# e0-dev-v006.net
KiCad netlist of a schematic drawn in EAGLE
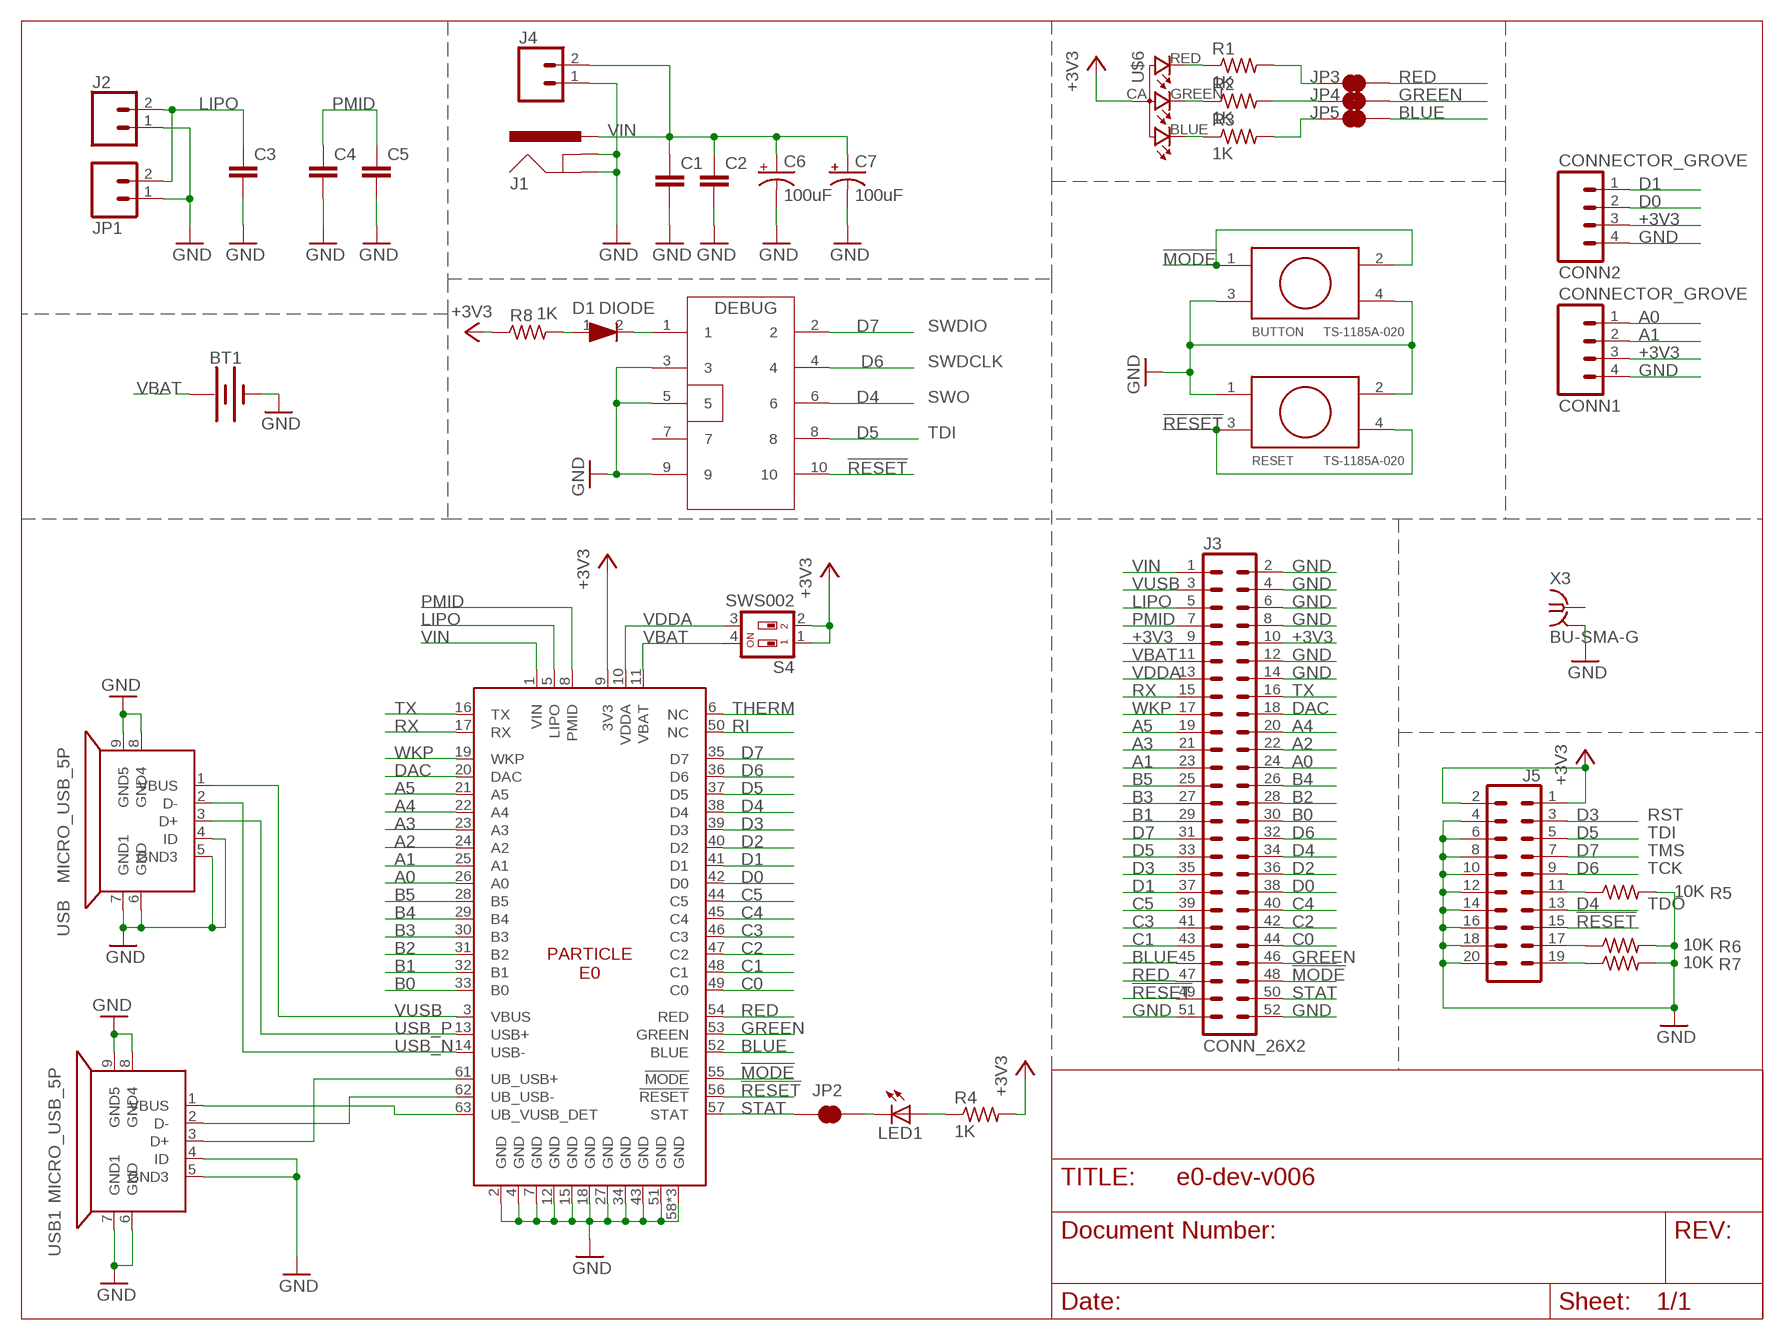
[diagram p0: schematic, sheet 1]

(export (version "E")
  (design (tool "Eeschema 10.0.6"))
  (components
    (comp (ref "BT1")
      (value "BATTERY-20MM_SMD")
      (footprint "eagle-import:BATTCON_20MM")
      (libsource (lib "eagle-import") (part "BATTERY-20MM_SMD"))
    )
    (comp (ref "BUTTON")
      (value "TS-1185A-020")
      (footprint "eagle-import:TS-1185A-020")
      (libsource (lib "eagle-import") (part "TS-1185A-020"))
    )
    (comp (ref "C1")
      (value "C-EUC0805")
      (footprint "eagle-import:C0805")
      (libsource (lib "eagle-import") (part "C-EUC0805"))
    )
    (comp (ref "C2")
      (value "C-EUC0805")
      (footprint "eagle-import:C0805")
      (libsource (lib "eagle-import") (part "C-EUC0805"))
    )
    (comp (ref "C3")
      (value "C-EUC0805")
      (footprint "eagle-import:C0805")
      (libsource (lib "eagle-import") (part "C-EUC0805"))
    )
    (comp (ref "C4")
      (value "C-EUC0805")
      (footprint "eagle-import:C0805")
      (libsource (lib "eagle-import") (part "C-EUC0805"))
    )
    (comp (ref "C5")
      (value "C-EUC0805")
      (footprint "eagle-import:C0805")
      (libsource (lib "eagle-import") (part "C-EUC0805"))
    )
    (comp (ref "C6")
      (value "100uF")
      (footprint "eagle-import:PANASONIC_D")
      (libsource (lib "eagle-import") (part "100UF-POLAR-25V-20%(ELEC)"))
    )
    (comp (ref "C7")
      (value "100uF")
      (footprint "eagle-import:PANASONIC_D")
      (libsource (lib "eagle-import") (part "100UF-POLAR-25V-20%(ELEC)"))
    )
    (comp (ref "CONN1")
      (value "CONNECTOR_GROVE")
      (footprint "eagle-import:CONNCTOR_GROVE")
      (libsource (lib "eagle-import") (part "CONNECTOR_GROVE"))
    )
    (comp (ref "CONN2")
      (value "CONNECTOR_GROVE")
      (footprint "eagle-import:CONNCTOR_GROVE")
      (libsource (lib "eagle-import") (part "CONNECTOR_GROVE"))
    )
    (comp (ref "D1")
      (value "DIODE")
      (footprint "eagle-import:SOD-323")
      (libsource (lib "eagle-import") (part "DIODESOD323"))
    )
    (comp (ref "DEBUG")
      (value "CON5X2")
      (footprint "eagle-import:CON5X2_1.27")
      (libsource (lib "eagle-import") (part "CON5X2"))
    )
    (comp (ref "J1")
      (value "POWER_JACKSLT")
      (footprint "eagle-import:POWER_JACK_SLOT")
      (libsource (lib "eagle-import") (part "POWER_JACKSLT"))
    )
    (comp (ref "J2")
      (value "CONN_021X02_NO_SILK")
      (footprint "eagle-import:1X02_NO_SILK")
      (libsource (lib "eagle-import") (part "CONN_021X02_NO_SILK"))
    )
    (comp (ref "J3")
      (value "CONN_26X2")
      (footprint "eagle-import:2X26")
      (libsource (lib "eagle-import") (part "CONN_26X2"))
    )
    (comp (ref "J4")
      (value "CONN_021X02_NO_SILK")
      (footprint "eagle-import:1X02_NO_SILK")
      (libsource (lib "eagle-import") (part "CONN_021X02_NO_SILK"))
    )
    (comp (ref "J5")
      (value "CONN_10X2NOSILK")
      (footprint "eagle-import:2X10_NOSILK")
      (libsource (lib "eagle-import") (part "CONN_10X2NOSILK"))
    )
    (comp (ref "JP1")
      (value "M02-JST-2MM-SMT")
      (footprint "eagle-import:JST-2-SMD@1")
      (libsource (lib "eagle-import") (part "M02-JST-2MM-SMT"))
    )
    (comp (ref "JP2")
      (value "JUMPER-SMT_2_NC_TRACE_NO-SILK")
      (footprint "eagle-import:SMT-JUMPER_2_NC_TRACE_NO-SILK")
      (libsource (lib "eagle-import") (part "JUMPER-SMT_2_NC_TRACE_NO-SILK"))
    )
    (comp (ref "JP3")
      (value "JUMPER-SMT_2_NC_TRACE_NO-SILK")
      (footprint "eagle-import:SMT-JUMPER_2_NC_TRACE_NO-SILK")
      (libsource (lib "eagle-import") (part "JUMPER-SMT_2_NC_TRACE_NO-SILK"))
    )
    (comp (ref "JP4")
      (value "JUMPER-SMT_2_NC_TRACE_NO-SILK")
      (footprint "eagle-import:SMT-JUMPER_2_NC_TRACE_NO-SILK")
      (libsource (lib "eagle-import") (part "JUMPER-SMT_2_NC_TRACE_NO-SILK"))
    )
    (comp (ref "JP5")
      (value "JUMPER-SMT_2_NC_TRACE_NO-SILK")
      (footprint "eagle-import:SMT-JUMPER_2_NC_TRACE_NO-SILK")
      (libsource (lib "eagle-import") (part "JUMPER-SMT_2_NC_TRACE_NO-SILK"))
    )
    (comp (ref "LED1")
      (value "LED0603")
      (footprint "eagle-import:LED-0603")
      (libsource (lib "eagle-import") (part "LED0603"))
    )
    (comp (ref "R1")
      (value "1K")
      (footprint "eagle-import:R0603")
      (libsource (lib "eagle-import") (part "R-US_R0603"))
    )
    (comp (ref "R2")
      (value "1K")
      (footprint "eagle-import:R0603")
      (libsource (lib "eagle-import") (part "R-US_R0603"))
    )
    (comp (ref "R3")
      (value "1K")
      (footprint "eagle-import:R0603")
      (libsource (lib "eagle-import") (part "R-US_R0603"))
    )
    (comp (ref "R4")
      (value "1K")
      (footprint "eagle-import:R0603")
      (libsource (lib "eagle-import") (part "R-US_R0603"))
    )
    (comp (ref "R5")
      (value "10K")
      (footprint "eagle-import:R0603")
      (libsource (lib "eagle-import") (part "R-US_R0603"))
    )
    (comp (ref "R6")
      (value "10K")
      (footprint "eagle-import:R0603")
      (libsource (lib "eagle-import") (part "R-US_R0603"))
    )
    (comp (ref "R7")
      (value "10K")
      (footprint "eagle-import:R0603")
      (libsource (lib "eagle-import") (part "R-US_R0603"))
    )
    (comp (ref "R8")
      (value "1K")
      (footprint "eagle-import:R0603")
      (libsource (lib "eagle-import") (part "R-US_R0603"))
    )
    (comp (ref "RESET")
      (value "TS-1185A-020")
      (footprint "eagle-import:TS-1185A-020")
      (libsource (lib "eagle-import") (part "TS-1185A-020"))
    )
    (comp (ref "S4")
      (value "SWS002")
      (footprint "eagle-import:SMS-002")
      (libsource (lib "eagle-import") (part "SWS002"))
    )
    (comp (ref "U$6")
      (value "RGB-LED-CLMVB-FKARGB")
      (footprint "eagle-import:PLCC4-2MM-RGB")
      (libsource (lib "eagle-import") (part "RGB-LED-CLMVB-FKARGB"))
    )
    (comp (ref "U1")
      (value "E0_V005")
      (footprint "eagle-import:E0")
      (libsource (lib "eagle-import") (part "E0_V005"))
    )
    (comp (ref "USB")
      (value "MICRO_USB_5P")
      (footprint "eagle-import:MICRO_USB")
      (libsource (lib "eagle-import") (part "MICRO_USBMICRO_USB"))
    )
    (comp (ref "USB1")
      (value "MICRO_USB_5P")
      (footprint "eagle-import:MICRO_USB")
      (libsource (lib "eagle-import") (part "MICRO_USBMICRO_USB"))
    )
    (comp (ref "X3")
      (value "BU-SMA-G")
      (footprint "eagle-import:BU-SMA-G")
      (libsource (lib "eagle-import") (part "BU-SMA-G"))
    )
  )
  (nets
    (net (code "1") (name "+3V3") (class "Default")
      (node (ref "CONN1") (pin "3") (pinfunction "3_3") (pintype "passive"))
      (node (ref "CONN2") (pin "3") (pinfunction "3_3") (pintype "passive"))
      (node (ref "J3") (pin "10") (pinfunction "10_10") (pintype "passive"))
      (node (ref "J3") (pin "9") (pinfunction "9_9") (pintype "passive"))
      (node (ref "J5") (pin "1") (pinfunction "1_1") (pintype "passive"))
      (node (ref "J5") (pin "2") (pinfunction "2_2") (pintype "passive"))
      (node (ref "R4") (pin "2") (pinfunction "2_2") (pintype "passive"))
      (node (ref "R8") (pin "1") (pinfunction "1_1") (pintype "passive"))
      (node (ref "S4") (pin "1") (pinfunction "1_1") (pintype "passive"))
      (node (ref "S4") (pin "2") (pinfunction "2_2") (pintype "passive"))
      (node (ref "U$6") (pin "CA") (pinfunction "1_CA") (pintype "passive"))
      (node (ref "U1") (pin "9") (pinfunction "3V3_9") (pintype "bidirectional"))
    )
    (net (code "2") (name "/A0") (class "Default")
      (node (ref "CONN1") (pin "1") (pinfunction "1_1") (pintype "passive"))
      (node (ref "J3") (pin "24") (pinfunction "24_24") (pintype "passive"))
      (node (ref "U1") (pin "26") (pinfunction "A0_26") (pintype "bidirectional"))
    )
    (net (code "3") (name "/A1") (class "Default")
      (node (ref "CONN1") (pin "2") (pinfunction "2_2") (pintype "passive"))
      (node (ref "J3") (pin "23") (pinfunction "23_23") (pintype "passive"))
      (node (ref "U1") (pin "25") (pinfunction "A1_25") (pintype "bidirectional"))
    )
    (net (code "4") (name "/A2") (class "Default")
      (node (ref "J3") (pin "22") (pinfunction "22_22") (pintype "passive"))
      (node (ref "U1") (pin "24") (pinfunction "A2_24") (pintype "bidirectional"))
    )
    (net (code "5") (name "/A3") (class "Default")
      (node (ref "J3") (pin "21") (pinfunction "21_21") (pintype "passive"))
      (node (ref "U1") (pin "23") (pinfunction "A3_23") (pintype "bidirectional"))
    )
    (net (code "6") (name "/A4") (class "Default")
      (node (ref "J3") (pin "20") (pinfunction "20_20") (pintype "passive"))
      (node (ref "U1") (pin "22") (pinfunction "A4_22") (pintype "bidirectional"))
    )
    (net (code "7") (name "/A5") (class "Default")
      (node (ref "J3") (pin "19") (pinfunction "19_19") (pintype "passive"))
      (node (ref "U1") (pin "21") (pinfunction "A5_21") (pintype "bidirectional"))
    )
    (net (code "8") (name "/B0") (class "Default")
      (node (ref "J3") (pin "30") (pinfunction "30_30") (pintype "passive"))
      (node (ref "U1") (pin "33") (pinfunction "B0_33") (pintype "bidirectional"))
    )
    (net (code "9") (name "/B1") (class "Default")
      (node (ref "J3") (pin "29") (pinfunction "29_29") (pintype "passive"))
      (node (ref "U1") (pin "32") (pinfunction "B1_32") (pintype "bidirectional"))
    )
    (net (code "10") (name "/B2") (class "Default")
      (node (ref "J3") (pin "28") (pinfunction "28_28") (pintype "passive"))
      (node (ref "U1") (pin "31") (pinfunction "B2_31") (pintype "bidirectional"))
    )
    (net (code "11") (name "/B3") (class "Default")
      (node (ref "J3") (pin "27") (pinfunction "27_27") (pintype "passive"))
      (node (ref "U1") (pin "30") (pinfunction "B3_30") (pintype "bidirectional"))
    )
    (net (code "12") (name "/B4") (class "Default")
      (node (ref "J3") (pin "26") (pinfunction "26_26") (pintype "passive"))
      (node (ref "U1") (pin "29") (pinfunction "B4_29") (pintype "bidirectional"))
    )
    (net (code "13") (name "/B5") (class "Default")
      (node (ref "J3") (pin "25") (pinfunction "25_25") (pintype "passive"))
      (node (ref "U1") (pin "28") (pinfunction "B5_28") (pintype "bidirectional"))
    )
    (net (code "14") (name "/BLUE") (class "Default")
      (node (ref "J3") (pin "45") (pinfunction "45_45") (pintype "passive"))
      (node (ref "JP5") (pin "2") (pinfunction "2_2") (pintype "passive"))
      (node (ref "U1") (pin "52") (pinfunction "BLUE_52") (pintype "bidirectional"))
    )
    (net (code "15") (name "/C0") (class "Default")
      (node (ref "J3") (pin "44") (pinfunction "44_44") (pintype "passive"))
      (node (ref "U1") (pin "49") (pinfunction "C0_49") (pintype "bidirectional"))
    )
    (net (code "16") (name "/C1") (class "Default")
      (node (ref "J3") (pin "43") (pinfunction "43_43") (pintype "passive"))
      (node (ref "U1") (pin "48") (pinfunction "C1_48") (pintype "bidirectional"))
    )
    (net (code "17") (name "/C2") (class "Default")
      (node (ref "J3") (pin "42") (pinfunction "42_42") (pintype "passive"))
      (node (ref "U1") (pin "47") (pinfunction "C2_47") (pintype "bidirectional"))
    )
    (net (code "18") (name "/C3") (class "Default")
      (node (ref "J3") (pin "41") (pinfunction "41_41") (pintype "passive"))
      (node (ref "U1") (pin "46") (pinfunction "C3_46") (pintype "bidirectional"))
    )
    (net (code "19") (name "/C4") (class "Default")
      (node (ref "J3") (pin "40") (pinfunction "40_40") (pintype "passive"))
      (node (ref "U1") (pin "45") (pinfunction "C4_45") (pintype "bidirectional"))
    )
    (net (code "20") (name "/C5") (class "Default")
      (node (ref "J3") (pin "39") (pinfunction "39_39") (pintype "passive"))
      (node (ref "U1") (pin "44") (pinfunction "C5_44") (pintype "bidirectional"))
    )
    (net (code "21") (name "/D0") (class "Default")
      (node (ref "CONN2") (pin "2") (pinfunction "2_2") (pintype "passive"))
      (node (ref "J3") (pin "38") (pinfunction "38_38") (pintype "passive"))
      (node (ref "U1") (pin "42") (pinfunction "D0_42") (pintype "bidirectional"))
    )
    (net (code "22") (name "/D1") (class "Default")
      (node (ref "CONN2") (pin "1") (pinfunction "1_1") (pintype "passive"))
      (node (ref "J3") (pin "37") (pinfunction "37_37") (pintype "passive"))
      (node (ref "U1") (pin "41") (pinfunction "D1_41") (pintype "bidirectional"))
    )
    (net (code "23") (name "/D2") (class "Default")
      (node (ref "J3") (pin "36") (pinfunction "36_36") (pintype "passive"))
      (node (ref "U1") (pin "40") (pinfunction "D2_40") (pintype "bidirectional"))
    )
    (net (code "24") (name "/D3") (class "Default")
      (node (ref "J3") (pin "35") (pinfunction "35_35") (pintype "passive"))
      (node (ref "J5") (pin "3") (pinfunction "3_3") (pintype "passive"))
      (node (ref "U1") (pin "39") (pinfunction "D3_39") (pintype "bidirectional"))
    )
    (net (code "25") (name "/D4") (class "Default")
      (node (ref "DEBUG") (pin "6") (pinfunction "6_6") (pintype "bidirectional"))
      (node (ref "J3") (pin "34") (pinfunction "34_34") (pintype "passive"))
      (node (ref "J5") (pin "13") (pinfunction "13_13") (pintype "passive"))
      (node (ref "U1") (pin "38") (pinfunction "D4_38") (pintype "bidirectional"))
    )
    (net (code "26") (name "/D5") (class "Default")
      (node (ref "DEBUG") (pin "8") (pinfunction "8_8") (pintype "bidirectional"))
      (node (ref "J3") (pin "33") (pinfunction "33_33") (pintype "passive"))
      (node (ref "J5") (pin "5") (pinfunction "5_5") (pintype "passive"))
      (node (ref "U1") (pin "37") (pinfunction "D5_37") (pintype "bidirectional"))
    )
    (net (code "27") (name "/D6") (class "Default")
      (node (ref "DEBUG") (pin "4") (pinfunction "4_4") (pintype "bidirectional"))
      (node (ref "J3") (pin "32") (pinfunction "32_32") (pintype "passive"))
      (node (ref "J5") (pin "9") (pinfunction "9_9") (pintype "passive"))
      (node (ref "U1") (pin "36") (pinfunction "D6_36") (pintype "bidirectional"))
    )
    (net (code "28") (name "/D7") (class "Default")
      (node (ref "DEBUG") (pin "2") (pinfunction "2_2") (pintype "bidirectional"))
      (node (ref "J3") (pin "31") (pinfunction "31_31") (pintype "passive"))
      (node (ref "J5") (pin "7") (pinfunction "7_7") (pintype "passive"))
      (node (ref "U1") (pin "35") (pinfunction "D7_35") (pintype "bidirectional"))
    )
    (net (code "29") (name "/DAC") (class "Default")
      (node (ref "J3") (pin "18") (pinfunction "18_18") (pintype "passive"))
      (node (ref "U1") (pin "20") (pinfunction "DAC_20") (pintype "bidirectional"))
    )
    (net (code "30") (name "/GREEN") (class "Default")
      (node (ref "J3") (pin "46") (pinfunction "46_46") (pintype "passive"))
      (node (ref "JP4") (pin "2") (pinfunction "2_2") (pintype "passive"))
      (node (ref "U1") (pin "53") (pinfunction "GREEN_53") (pintype "bidirectional"))
    )
    (net (code "31") (name "/LIPO") (class "Default")
      (node (ref "C3") (pin "1") (pinfunction "1_1") (pintype "passive"))
      (node (ref "J2") (pin "2") (pinfunction "2_2") (pintype "passive"))
      (node (ref "J3") (pin "5") (pinfunction "5_5") (pintype "passive"))
      (node (ref "JP1") (pin "2") (pinfunction "1_2") (pintype "passive"))
      (node (ref "U1") (pin "5") (pinfunction "LIPO_5") (pintype "bidirectional"))
    )
    (net (code "32") (name "/PMID") (class "Default")
      (node (ref "C4") (pin "1") (pinfunction "1_1") (pintype "passive"))
      (node (ref "C5") (pin "1") (pinfunction "1_1") (pintype "passive"))
      (node (ref "J3") (pin "7") (pinfunction "7_7") (pintype "passive"))
      (node (ref "U1") (pin "8") (pinfunction "PMID_8") (pintype "bidirectional"))
    )
    (net (code "33") (name "/RED") (class "Default")
      (node (ref "J3") (pin "47") (pinfunction "47_47") (pintype "passive"))
      (node (ref "JP3") (pin "2") (pinfunction "2_2") (pintype "passive"))
      (node (ref "U1") (pin "54") (pinfunction "RED_54") (pintype "bidirectional"))
    )
    (net (code "34") (name "/RI") (class "Default")
      (node (ref "U1") (pin "50") (pinfunction "NC_50") (pintype "bidirectional"))
    )
    (net (code "35") (name "/RX") (class "Default")
      (node (ref "J3") (pin "15") (pinfunction "15_15") (pintype "passive"))
      (node (ref "U1") (pin "17") (pinfunction "RX_17") (pintype "bidirectional"))
    )
    (net (code "36") (name "/STAT") (class "Default")
      (node (ref "J3") (pin "50") (pinfunction "50_50") (pintype "passive"))
      (node (ref "JP2") (pin "1") (pinfunction "1_1") (pintype "passive"))
      (node (ref "U1") (pin "57") (pinfunction "STAT_57") (pintype "bidirectional"))
    )
    (net (code "37") (name "/THERM") (class "Default")
      (node (ref "U1") (pin "6") (pinfunction "NC_6") (pintype "bidirectional"))
    )
    (net (code "38") (name "/TX") (class "Default")
      (node (ref "J3") (pin "16") (pinfunction "16_16") (pintype "passive"))
      (node (ref "U1") (pin "16") (pinfunction "TX_16") (pintype "bidirectional"))
    )
    (net (code "39") (name "/USB_N") (class "Default")
      (node (ref "U1") (pin "14") (pinfunction "USB-_14") (pintype "bidirectional"))
      (node (ref "USB") (pin "2") (pinfunction "D-_2") (pintype "bidirectional"))
    )
    (net (code "40") (name "/USB_P") (class "Default")
      (node (ref "U1") (pin "13") (pinfunction "USB+_13") (pintype "bidirectional"))
      (node (ref "USB") (pin "3") (pinfunction "D+_3") (pintype "bidirectional"))
    )
    (net (code "41") (name "/VBAT") (class "Default")
      (node (ref "BT1") (pin "1") (pinfunction "+_1") (pintype "power_in"))
      (node (ref "J3") (pin "11") (pinfunction "11_11") (pintype "passive"))
      (node (ref "S4") (pin "4") (pinfunction "4_4") (pintype "passive"))
      (node (ref "U1") (pin "11") (pinfunction "VBAT_11") (pintype "bidirectional"))
    )
    (net (code "42") (name "/VDDA") (class "Default")
      (node (ref "J3") (pin "13") (pinfunction "13_13") (pintype "passive"))
      (node (ref "S4") (pin "3") (pinfunction "3_3") (pintype "passive"))
      (node (ref "U1") (pin "10") (pinfunction "VDDA_10") (pintype "bidirectional"))
    )
    (net (code "43") (name "/VIN") (class "Default")
      (node (ref "C1") (pin "1") (pinfunction "1_1") (pintype "passive"))
      (node (ref "C2") (pin "1") (pinfunction "1_1") (pintype "passive"))
      (node (ref "C6") (pin "+") (pinfunction "+_+") (pintype "passive"))
      (node (ref "C7") (pin "+") (pinfunction "+_+") (pintype "passive"))
      (node (ref "J1") (pin "PWR") (pinfunction "PWR_PWR") (pintype "bidirectional"))
      (node (ref "J3") (pin "1") (pinfunction "1_1") (pintype "passive"))
      (node (ref "J4") (pin "2") (pinfunction "2_2") (pintype "passive"))
      (node (ref "U1") (pin "1") (pinfunction "VIN_1") (pintype "bidirectional"))
    )
    (net (code "44") (name "/VUSB") (class "Default")
      (node (ref "J3") (pin "3") (pinfunction "3_3") (pintype "passive"))
      (node (ref "U1") (pin "3") (pinfunction "VBUS_3") (pintype "bidirectional"))
      (node (ref "USB") (pin "1") (pinfunction "VBUS_1") (pintype "bidirectional"))
    )
    (net (code "45") (name "/WKP") (class "Default")
      (node (ref "J3") (pin "17") (pinfunction "17_17") (pintype "passive"))
      (node (ref "U1") (pin "19") (pinfunction "WKP_19") (pintype "bidirectional"))
    )
    (net (code "46") (name "/~{MODE}") (class "Default")
      (node (ref "BUTTON") (pin "1") (pinfunction "P$1_1") (pintype "bidirectional"))
      (node (ref "BUTTON") (pin "2") (pinfunction "P$2_2") (pintype "bidirectional"))
      (node (ref "J3") (pin "48") (pinfunction "48_48") (pintype "passive"))
      (node (ref "U1") (pin "55") (pinfunction "~{MODE}_55") (pintype "bidirectional"))
    )
    (net (code "47") (name "/~{RESET}") (class "Default")
      (node (ref "DEBUG") (pin "10") (pinfunction "10_10") (pintype "bidirectional"))
      (node (ref "J3") (pin "49") (pinfunction "49_49") (pintype "passive"))
      (node (ref "J5") (pin "15") (pinfunction "15_15") (pintype "passive"))
      (node (ref "RESET") (pin "3") (pinfunction "P$3_3") (pintype "bidirectional"))
      (node (ref "RESET") (pin "4") (pinfunction "P$4_4") (pintype "bidirectional"))
      (node (ref "U1") (pin "56") (pinfunction "~{RESET}_56") (pintype "bidirectional"))
    )
    (net (code "48") (name "GND") (class "Default")
      (node (ref "BT1") (pin "2") (pinfunction "-_2") (pintype "power_in"))
      (node (ref "BUTTON") (pin "3") (pinfunction "P$3_3") (pintype "bidirectional"))
      (node (ref "BUTTON") (pin "4") (pinfunction "P$4_4") (pintype "bidirectional"))
      (node (ref "C1") (pin "2") (pinfunction "2_2") (pintype "passive"))
      (node (ref "C2") (pin "2") (pinfunction "2_2") (pintype "passive"))
      (node (ref "C3") (pin "2") (pinfunction "2_2") (pintype "passive"))
      (node (ref "C4") (pin "2") (pinfunction "2_2") (pintype "passive"))
      (node (ref "C5") (pin "2") (pinfunction "2_2") (pintype "passive"))
      (node (ref "C6") (pin "-") (pinfunction "-_-") (pintype "passive"))
      (node (ref "C7") (pin "-") (pinfunction "-_-") (pintype "passive"))
      (node (ref "CONN1") (pin "4") (pinfunction "4_4") (pintype "passive"))
      (node (ref "CONN2") (pin "4") (pinfunction "4_4") (pintype "passive"))
      (node (ref "DEBUG") (pin "3") (pinfunction "3_3") (pintype "bidirectional"))
      (node (ref "DEBUG") (pin "5") (pinfunction "5_5") (pintype "bidirectional"))
      (node (ref "DEBUG") (pin "9") (pinfunction "9_9") (pintype "bidirectional"))
      (node (ref "J1") (pin "GND@1") (pinfunction "GNDBREAK_GND@1") (pintype "bidirectional"))
      (node (ref "J1") (pin "GND@2") (pinfunction "GND_GND@2") (pintype "bidirectional"))
      (node (ref "J2") (pin "1") (pinfunction "1_1") (pintype "passive"))
      (node (ref "J3") (pin "12") (pinfunction "12_12") (pintype "passive"))
      (node (ref "J3") (pin "14") (pinfunction "14_14") (pintype "passive"))
      (node (ref "J3") (pin "2") (pinfunction "2_2") (pintype "passive"))
      (node (ref "J3") (pin "4") (pinfunction "4_4") (pintype "passive"))
      (node (ref "J3") (pin "51") (pinfunction "51_51") (pintype "passive"))
      (node (ref "J3") (pin "52") (pinfunction "52_52") (pintype "passive"))
      (node (ref "J3") (pin "6") (pinfunction "6_6") (pintype "passive"))
      (node (ref "J3") (pin "8") (pinfunction "8_8") (pintype "passive"))
      (node (ref "J4") (pin "1") (pinfunction "1_1") (pintype "passive"))
      (node (ref "J5") (pin "10") (pinfunction "10_10") (pintype "passive"))
      (node (ref "J5") (pin "12") (pinfunction "12_12") (pintype "passive"))
      (node (ref "J5") (pin "14") (pinfunction "14_14") (pintype "passive"))
      (node (ref "J5") (pin "16") (pinfunction "16_16") (pintype "passive"))
      (node (ref "J5") (pin "18") (pinfunction "18_18") (pintype "passive"))
      (node (ref "J5") (pin "20") (pinfunction "20_20") (pintype "passive"))
      (node (ref "J5") (pin "4") (pinfunction "4_4") (pintype "passive"))
      (node (ref "J5") (pin "6") (pinfunction "6_6") (pintype "passive"))
      (node (ref "J5") (pin "8") (pinfunction "8_8") (pintype "passive"))
      (node (ref "JP1") (pin "1") (pinfunction "2_1") (pintype "passive"))
      (node (ref "R5") (pin "2") (pinfunction "2_2") (pintype "passive"))
      (node (ref "R6") (pin "2") (pinfunction "2_2") (pintype "passive"))
      (node (ref "R7") (pin "2") (pinfunction "2_2") (pintype "passive"))
      (node (ref "RESET") (pin "1") (pinfunction "P$1_1") (pintype "bidirectional"))
      (node (ref "RESET") (pin "2") (pinfunction "P$2_2") (pintype "bidirectional"))
      (node (ref "U1") (pin "12") (pinfunction "GND_12") (pintype "bidirectional"))
      (node (ref "U1") (pin "15") (pinfunction "GND_15") (pintype "bidirectional"))
      (node (ref "U1") (pin "18") (pinfunction "GND_18") (pintype "bidirectional"))
      (node (ref "U1") (pin "2") (pinfunction "GND_2") (pintype "bidirectional"))
      (node (ref "U1") (pin "27") (pinfunction "GND_27") (pintype "bidirectional"))
      (node (ref "U1") (pin "34") (pinfunction "GND_34") (pintype "bidirectional"))
      (node (ref "U1") (pin "4") (pinfunction "GND_4") (pintype "bidirectional"))
      (node (ref "U1") (pin "43") (pinfunction "GND_43") (pintype "bidirectional"))
      (node (ref "U1") (pin "51") (pinfunction "GND_51") (pintype "bidirectional"))
      (node (ref "U1") (pin "58") (pinfunction "GND_58") (pintype "bidirectional"))
      (node (ref "U1") (pin "59") (pinfunction "GND_59") (pintype "bidirectional"))
      (node (ref "U1") (pin "60") (pinfunction "GND_60") (pintype "bidirectional"))
      (node (ref "U1") (pin "7") (pinfunction "GND_7") (pintype "bidirectional"))
      (node (ref "USB") (pin "4") (pinfunction "ID_4") (pintype "bidirectional"))
      (node (ref "USB") (pin "5") (pinfunction "GND3_5") (pintype "bidirectional"))
      (node (ref "USB") (pin "6") (pinfunction "GND_6") (pintype "bidirectional"))
      (node (ref "USB") (pin "7") (pinfunction "GND1_7") (pintype "bidirectional"))
      (node (ref "USB") (pin "8") (pinfunction "GND4_8") (pintype "bidirectional"))
      (node (ref "USB") (pin "9") (pinfunction "GND5_9") (pintype "bidirectional"))
      (node (ref "USB1") (pin "4") (pinfunction "ID_4") (pintype "bidirectional"))
      (node (ref "USB1") (pin "5") (pinfunction "GND3_5") (pintype "bidirectional"))
      (node (ref "USB1") (pin "6") (pinfunction "GND_6") (pintype "bidirectional"))
      (node (ref "USB1") (pin "7") (pinfunction "GND1_7") (pintype "bidirectional"))
      (node (ref "USB1") (pin "8") (pinfunction "GND4_8") (pintype "bidirectional"))
      (node (ref "USB1") (pin "9") (pinfunction "GND5_9") (pintype "bidirectional"))
      (node (ref "X3") (pin "2") (pinfunction "2_2") (pintype "passive"))
      (node (ref "X3") (pin "3") (pinfunction "2_3") (pintype "passive"))
      (node (ref "X3") (pin "4") (pinfunction "2_4") (pintype "passive"))
      (node (ref "X3") (pin "5") (pinfunction "2_5") (pintype "passive"))
    )
    (net (code "49") (name "Net-(D1-P$1)") (class "Default")
      (node (ref "D1") (pin "1") (pinfunction "P$1_1") (pintype "bidirectional"))
      (node (ref "R8") (pin "2") (pinfunction "2_2") (pintype "passive"))
    )
    (net (code "50") (name "Net-(D1-P$2)") (class "Default")
      (node (ref "D1") (pin "2") (pinfunction "P$2_2") (pintype "bidirectional"))
      (node (ref "DEBUG") (pin "1") (pinfunction "1_1") (pintype "bidirectional"))
    )
    (net (code "51") (name "Net-(J5-Pad11)") (class "Default")
      (node (ref "J5") (pin "11") (pinfunction "11_11") (pintype "passive"))
      (node (ref "R5") (pin "1") (pinfunction "1_1") (pintype "passive"))
    )
    (net (code "52") (name "Net-(J5-Pad17)") (class "Default")
      (node (ref "J5") (pin "17") (pinfunction "17_17") (pintype "passive"))
      (node (ref "R6") (pin "1") (pinfunction "1_1") (pintype "passive"))
    )
    (net (code "53") (name "Net-(J5-Pad19)") (class "Default")
      (node (ref "J5") (pin "19") (pinfunction "19_19") (pintype "passive"))
      (node (ref "R7") (pin "1") (pinfunction "1_1") (pintype "passive"))
    )
    (net (code "54") (name "Net-(JP2-Pad2)") (class "Default")
      (node (ref "JP2") (pin "2") (pinfunction "2_2") (pintype "passive"))
      (node (ref "LED1") (pin "C") (pinfunction "C_C") (pintype "passive"))
    )
    (net (code "55") (name "Net-(JP3-Pad1)") (class "Default")
      (node (ref "JP3") (pin "1") (pinfunction "1_1") (pintype "passive"))
      (node (ref "R1") (pin "2") (pinfunction "2_2") (pintype "passive"))
    )
    (net (code "56") (name "Net-(JP4-Pad1)") (class "Default")
      (node (ref "JP4") (pin "1") (pinfunction "1_1") (pintype "passive"))
      (node (ref "R2") (pin "2") (pinfunction "2_2") (pintype "passive"))
    )
    (net (code "57") (name "Net-(JP5-Pad1)") (class "Default")
      (node (ref "JP5") (pin "1") (pinfunction "1_1") (pintype "passive"))
      (node (ref "R3") (pin "2") (pinfunction "2_2") (pintype "passive"))
    )
    (net (code "58") (name "Net-(LED1-PadA)") (class "Default")
      (node (ref "LED1") (pin "A") (pinfunction "A_A") (pintype "passive"))
      (node (ref "R4") (pin "1") (pinfunction "1_1") (pintype "passive"))
    )
    (net (code "59") (name "Net-(U$6-2)") (class "Default")
      (node (ref "R3") (pin "1") (pinfunction "1_1") (pintype "passive"))
      (node (ref "U$6") (pin "BLUE") (pinfunction "2_BLUE") (pintype "passive"))
    )
    (net (code "60") (name "Net-(U$6-3)") (class "Default")
      (node (ref "R2") (pin "1") (pinfunction "1_1") (pintype "passive"))
      (node (ref "U$6") (pin "GREEN") (pinfunction "3_GREEN") (pintype "passive"))
    )
    (net (code "61") (name "Net-(U$6-4)") (class "Default")
      (node (ref "R1") (pin "1") (pinfunction "1_1") (pintype "passive"))
      (node (ref "U$6") (pin "RED") (pinfunction "4_RED") (pintype "passive"))
    )
    (net (code "62") (name "Net-(U1-UB_USB+)") (class "Default")
      (node (ref "U1") (pin "61") (pinfunction "UB_USB+_61") (pintype "bidirectional"))
      (node (ref "USB1") (pin "3") (pinfunction "D+_3") (pintype "bidirectional"))
    )
    (net (code "63") (name "Net-(U1-UB_USB-)") (class "Default")
      (node (ref "U1") (pin "62") (pinfunction "UB_USB-_62") (pintype "bidirectional"))
      (node (ref "USB1") (pin "2") (pinfunction "D-_2") (pintype "bidirectional"))
    )
    (net (code "64") (name "Net-(U1-UB_VUSB_DET)") (class "Default")
      (node (ref "U1") (pin "63") (pinfunction "UB_VUSB_DET_63") (pintype "bidirectional"))
      (node (ref "USB1") (pin "1") (pinfunction "VBUS_1") (pintype "bidirectional"))
    )
    (net (code "65") (name "unconnected-(DEBUG-Pad7)") (class "Default")
      (node (ref "DEBUG") (pin "7") (pinfunction "7_7") (pintype "bidirectional"))
    )
    (net (code "66") (name "unconnected-(X3-Pad1)") (class "Default")
      (node (ref "X3") (pin "1") (pinfunction "1_1") (pintype "passive"))
    )
  )
)
